# PATHOS_DriveConnectors.net
KiCad netlist of a schematic drawn in Altium Designer
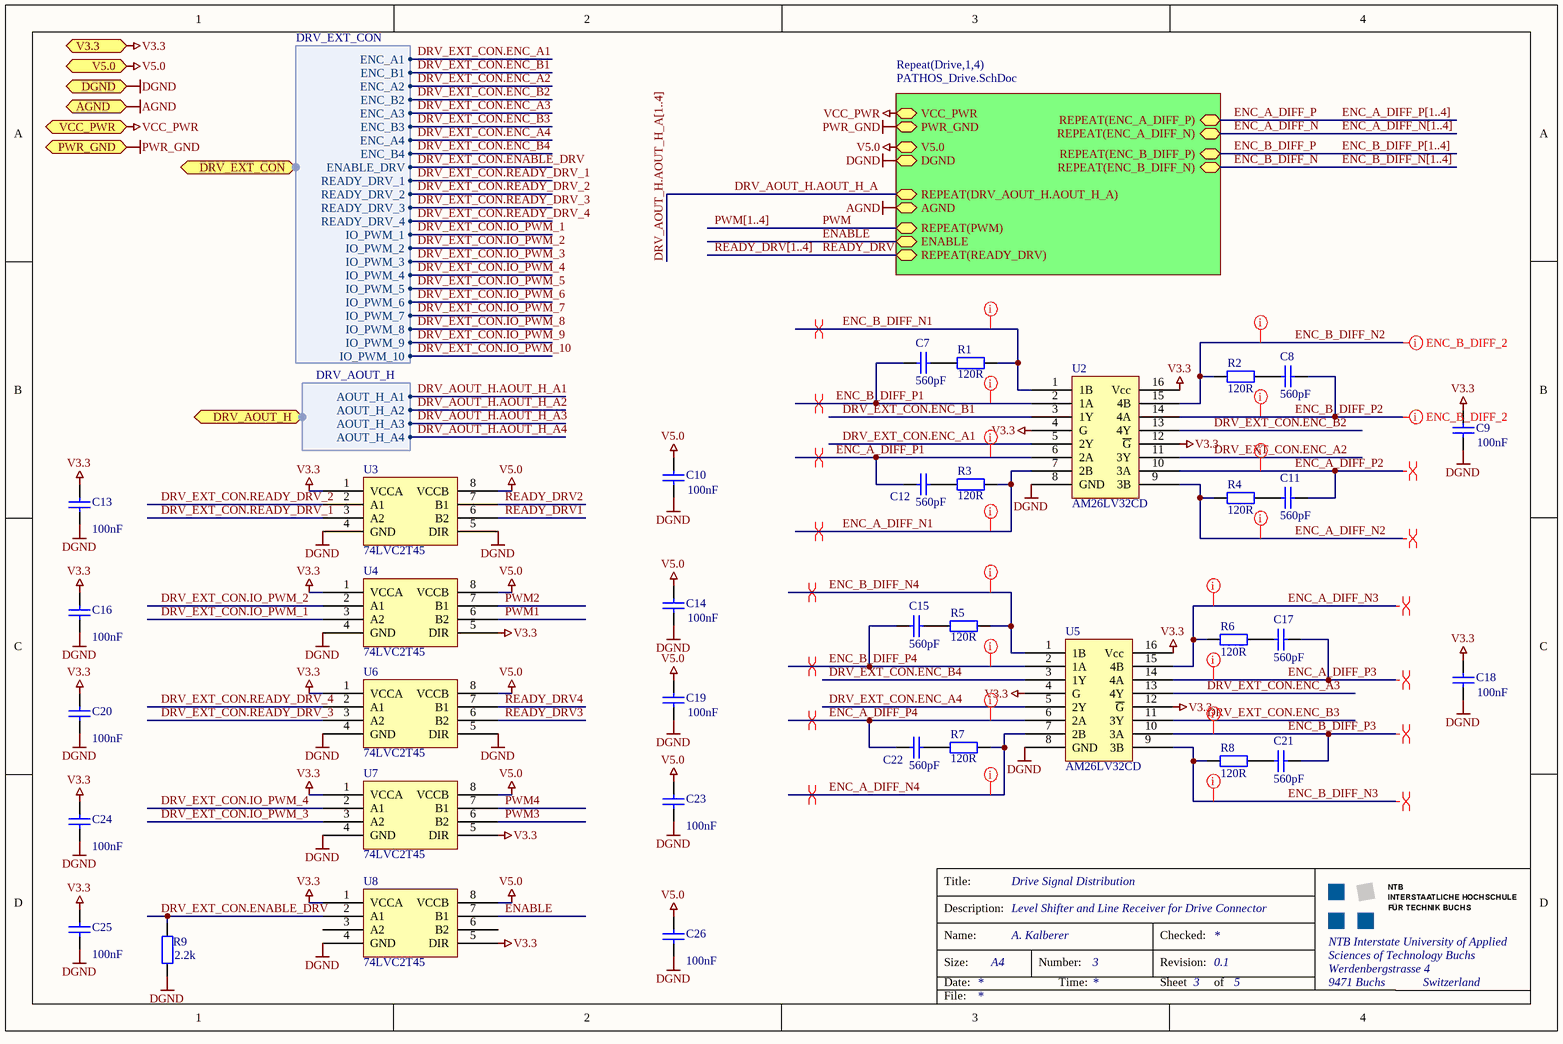
[diagram p0: PATHOS_DriveConnectors.SchDoc]

(export (version "E")
  (design (tool "Eeschema 10.0.6"))
  (components
    (comp (ref "C7")
      (value "560pF")
      (footprint "0603_3D")
      (description "Capacitor")
      (fields (field (name "Comment") "Cap") (field (name "PUBLISHER") "Altium Limited"))
      (libsource (lib "Miscellaneous Devices") (part "Cap"))
    )
    (comp (ref "C8")
      (value "560pF")
      (footprint "0603_3D")
      (description "Capacitor")
      (fields (field (name "Comment") "Cap") (field (name "PUBLISHER") "Altium Limited"))
      (libsource (lib "Miscellaneous Devices") (part "Cap"))
    )
    (comp (ref "C9")
      (value "100nF")
      (footprint "0603_3D")
      (description "Capacitor")
      (fields (field (name "Comment") "Cap") (field (name "PUBLISHER") "Altium Limited"))
      (libsource (lib "Miscellaneous Devices") (part "Cap"))
    )
    (comp (ref "C10")
      (value "100nF")
      (footprint "0603_3D")
      (description "Capacitor")
      (fields (field (name "Comment") "Cap") (field (name "PUBLISHER") "Altium Limited"))
      (libsource (lib "Miscellaneous Devices") (part "Cap"))
    )
    (comp (ref "C11")
      (value "560pF")
      (footprint "0603_3D")
      (description "Capacitor")
      (fields (field (name "Comment") "Cap") (field (name "PUBLISHER") "Altium Limited"))
      (libsource (lib "Miscellaneous Devices") (part "Cap"))
    )
    (comp (ref "C12")
      (value "560pF")
      (footprint "0603_3D")
      (description "Capacitor")
      (fields (field (name "Comment") "Cap") (field (name "PUBLISHER") "Altium Limited"))
      (libsource (lib "Miscellaneous Devices") (part "Cap"))
    )
    (comp (ref "C13")
      (value "100nF")
      (footprint "0603_3D")
      (description "Capacitor")
      (fields (field (name "Comment") "Cap") (field (name "PUBLISHER") "Altium Limited"))
      (libsource (lib "Miscellaneous Devices") (part "Cap"))
    )
    (comp (ref "C14")
      (value "100nF")
      (footprint "0603_3D")
      (description "Capacitor")
      (fields (field (name "Comment") "Cap") (field (name "PUBLISHER") "Altium Limited"))
      (libsource (lib "Miscellaneous Devices") (part "Cap"))
    )
    (comp (ref "C15")
      (value "560pF")
      (footprint "0603_3D")
      (description "Capacitor")
      (fields (field (name "Comment") "Cap") (field (name "PUBLISHER") "Altium Limited"))
      (libsource (lib "Miscellaneous Devices") (part "Cap"))
    )
    (comp (ref "C16")
      (value "100nF")
      (footprint "0603_3D")
      (description "Capacitor")
      (fields (field (name "Comment") "Cap") (field (name "PUBLISHER") "Altium Limited"))
      (libsource (lib "Miscellaneous Devices") (part "Cap"))
    )
    (comp (ref "C17")
      (value "560pF")
      (footprint "0603_3D")
      (description "Capacitor")
      (fields (field (name "Comment") "Cap") (field (name "PUBLISHER") "Altium Limited"))
      (libsource (lib "Miscellaneous Devices") (part "Cap"))
    )
    (comp (ref "C18")
      (value "100nF")
      (footprint "0603_3D")
      (description "Capacitor")
      (fields (field (name "Comment") "Cap") (field (name "PUBLISHER") "Altium Limited"))
      (libsource (lib "Miscellaneous Devices") (part "Cap"))
    )
    (comp (ref "C19")
      (value "100nF")
      (footprint "0603_3D")
      (description "Capacitor")
      (fields (field (name "Comment") "Cap") (field (name "PUBLISHER") "Altium Limited"))
      (libsource (lib "Miscellaneous Devices") (part "Cap"))
    )
    (comp (ref "C20")
      (value "100nF")
      (footprint "0603_3D")
      (description "Capacitor")
      (fields (field (name "Comment") "Cap") (field (name "PUBLISHER") "Altium Limited"))
      (libsource (lib "Miscellaneous Devices") (part "Cap"))
    )
    (comp (ref "C21")
      (value "560pF")
      (footprint "0603_3D")
      (description "Capacitor")
      (fields (field (name "Comment") "Cap") (field (name "PUBLISHER") "Altium Limited"))
      (libsource (lib "Miscellaneous Devices") (part "Cap"))
    )
    (comp (ref "C22")
      (value "560pF")
      (footprint "0603_3D")
      (description "Capacitor")
      (fields (field (name "Comment") "Cap") (field (name "PUBLISHER") "Altium Limited"))
      (libsource (lib "Miscellaneous Devices") (part "Cap"))
    )
    (comp (ref "C23")
      (value "100nF")
      (footprint "0603_3D")
      (description "Capacitor")
      (fields (field (name "Comment") "Cap") (field (name "PUBLISHER") "Altium Limited"))
      (libsource (lib "Miscellaneous Devices") (part "Cap"))
    )
    (comp (ref "C24")
      (value "100nF")
      (footprint "0603_3D")
      (description "Capacitor")
      (fields (field (name "Comment") "Cap") (field (name "PUBLISHER") "Altium Limited"))
      (libsource (lib "Miscellaneous Devices") (part "Cap"))
    )
    (comp (ref "C25")
      (value "100nF")
      (footprint "0603_3D")
      (description "Capacitor")
      (fields (field (name "Comment") "Cap") (field (name "PUBLISHER") "Altium Limited"))
      (libsource (lib "Miscellaneous Devices") (part "Cap"))
    )
    (comp (ref "C26")
      (value "100nF")
      (footprint "0603_3D")
      (description "Capacitor")
      (fields (field (name "Comment") "Cap") (field (name "PUBLISHER") "Altium Limited"))
      (libsource (lib "Miscellaneous Devices") (part "Cap"))
    )
    (comp (ref "R1")
      (value "120R")
      (footprint "0603_3D")
      (description "Resistor")
      (fields (field (name "Comment") "Res2") (field (name "PUBLISHER") "Altium Limited"))
      (libsource (lib "") (part "Res2_1"))
    )
    (comp (ref "R2")
      (value "120R")
      (footprint "0603_3D")
      (description "Resistor")
      (fields (field (name "Comment") "Res2") (field (name "PUBLISHER") "Altium Limited"))
      (libsource (lib "Miscellaneous Devices") (part "Res2"))
    )
    (comp (ref "R3")
      (value "120R")
      (footprint "0603_3D")
      (description "Resistor")
      (fields (field (name "Comment") "Res2") (field (name "PUBLISHER") "Altium Limited"))
      (libsource (lib "") (part "Res2_1"))
    )
    (comp (ref "R4")
      (value "120R")
      (footprint "0603_3D")
      (description "Resistor")
      (fields (field (name "Comment") "Res2") (field (name "PUBLISHER") "Altium Limited"))
      (libsource (lib "Miscellaneous Devices") (part "Res2"))
    )
    (comp (ref "R5")
      (value "120R")
      (footprint "0603_3D")
      (description "Resistor")
      (fields (field (name "Comment") "Res2") (field (name "PUBLISHER") "Altium Limited"))
      (libsource (lib "") (part "Res2_1"))
    )
    (comp (ref "R6")
      (value "120R")
      (footprint "0603_3D")
      (description "Resistor")
      (fields (field (name "Comment") "Res2") (field (name "PUBLISHER") "Altium Limited"))
      (libsource (lib "Miscellaneous Devices") (part "Res2"))
    )
    (comp (ref "R7")
      (value "120R")
      (footprint "0603_3D")
      (description "Resistor")
      (fields (field (name "Comment") "Res2") (field (name "PUBLISHER") "Altium Limited"))
      (libsource (lib "") (part "Res2_1"))
    )
    (comp (ref "R8")
      (value "120R")
      (footprint "0603_3D")
      (description "Resistor")
      (fields (field (name "Comment") "Res2") (field (name "PUBLISHER") "Altium Limited"))
      (libsource (lib "Miscellaneous Devices") (part "Res2"))
    )
    (comp (ref "R9")
      (value "2.2k")
      (footprint "0603_3D")
      (description "Resistor")
      (fields (field (name "Comment") "Res2") (field (name "PUBLISHER") "Altium Limited"))
      (libsource (lib "") (part "Res2_2"))
    )
    (comp (ref "U2")
      (value "AM26LV32CD")
      (footprint "SOP16")
      (libsource (lib "Pathos_Div") (part "AM26LV32CD"))
    )
    (comp (ref "U3")
      (value "74LVC2T45")
      (footprint "74LVC2T45")
      (description "SN74LVC2T45DCTR")
      (libsource (lib "Pathos_Div") (part "74LVC2T45"))
    )
    (comp (ref "U4")
      (value "74LVC2T45")
      (footprint "74LVC2T45")
      (description "SN74LVC2T45DCTR")
      (libsource (lib "Pathos_Div") (part "74LVC2T45"))
    )
    (comp (ref "U5")
      (value "AM26LV32CD")
      (footprint "SOP16")
      (libsource (lib "Pathos_Div") (part "AM26LV32CD"))
    )
    (comp (ref "U6")
      (value "74LVC2T45")
      (footprint "74LVC2T45")
      (description "SN74LVC2T45DCTR")
      (libsource (lib "Pathos_Div") (part "74LVC2T45"))
    )
    (comp (ref "U7")
      (value "74LVC2T45")
      (footprint "74LVC2T45")
      (description "SN74LVC2T45DCTR")
      (libsource (lib "Pathos_Div") (part "74LVC2T45"))
    )
    (comp (ref "U8")
      (value "74LVC2T45")
      (footprint "74LVC2T45")
      (description "SN74LVC2T45DCTR")
      (libsource (lib "Pathos_Div") (part "74LVC2T45"))
    )
  )
  (nets
    (net (code "9") (name "/DRV_EXT_CON.ENABLE_DRV") (class "Default")
      (node (ref "R9") (pin "2") (pinfunction "2_2") (pintype "passive"))
      (node (ref "U8") (pin "2") (pinfunction "A1_2") (pintype "passive"))
    )
    (net (code "10") (name "/DRV_EXT_CON.ENC_A1") (class "Default")
      (node (ref "U2") (pin "5") (pinfunction "2Y_5") (pintype "passive"))
    )
    (net (code "11") (name "/DRV_EXT_CON.ENC_A2") (class "Default")
      (node (ref "U2") (pin "11") (pinfunction "3Y_11") (pintype "passive"))
    )
    (net (code "12") (name "/DRV_EXT_CON.ENC_A3") (class "Default")
      (node (ref "U5") (pin "13") (pinfunction "4Y_13") (pintype "passive"))
    )
    (net (code "13") (name "/DRV_EXT_CON.ENC_A4") (class "Default")
      (node (ref "U5") (pin "5") (pinfunction "2Y_5") (pintype "passive"))
    )
    (net (code "14") (name "/DRV_EXT_CON.ENC_B1") (class "Default")
      (node (ref "U2") (pin "3") (pinfunction "1Y_3") (pintype "passive"))
    )
    (net (code "15") (name "/DRV_EXT_CON.ENC_B2") (class "Default")
      (node (ref "U2") (pin "13") (pinfunction "4Y_13") (pintype "passive"))
    )
    (net (code "16") (name "/DRV_EXT_CON.ENC_B3") (class "Default")
      (node (ref "U5") (pin "11") (pinfunction "3Y_11") (pintype "passive"))
    )
    (net (code "17") (name "/DRV_EXT_CON.ENC_B4") (class "Default")
      (node (ref "U5") (pin "3") (pinfunction "1Y_3") (pintype "passive"))
    )
    (net (code "18") (name "/DRV_EXT_CON.IO_PWM_1") (class "Default")
      (node (ref "U4") (pin "3") (pinfunction "A2_3") (pintype "passive"))
    )
    (net (code "19") (name "/DRV_EXT_CON.IO_PWM_2") (class "Default")
      (node (ref "U4") (pin "2") (pinfunction "A1_2") (pintype "passive"))
    )
    (net (code "20") (name "/DRV_EXT_CON.IO_PWM_3") (class "Default")
      (node (ref "U7") (pin "3") (pinfunction "A2_3") (pintype "passive"))
    )
    (net (code "21") (name "/DRV_EXT_CON.IO_PWM_4") (class "Default")
      (node (ref "U7") (pin "2") (pinfunction "A1_2") (pintype "passive"))
    )
    (net (code "28") (name "/DRV_EXT_CON.READY_DRV_1") (class "Default")
      (node (ref "U3") (pin "3") (pinfunction "A2_3") (pintype "passive"))
    )
    (net (code "29") (name "/DRV_EXT_CON.READY_DRV_2") (class "Default")
      (node (ref "U3") (pin "2") (pinfunction "A1_2") (pintype "passive"))
    )
    (net (code "30") (name "/DRV_EXT_CON.READY_DRV_3") (class "Default")
      (node (ref "U6") (pin "3") (pinfunction "A2_3") (pintype "passive"))
    )
    (net (code "31") (name "/DRV_EXT_CON.READY_DRV_4") (class "Default")
      (node (ref "U6") (pin "2") (pinfunction "A1_2") (pintype "passive"))
    )
    (net (code "32") (name "/ENABLE") (class "Default")
      (node (ref "U8") (pin "7") (pinfunction "B1_7") (pintype "passive"))
    )
    (net (code "34") (name "/ENC_A_DIFF_N1") (class "Default")
      (node (ref "R3") (pin "1") (pinfunction "1_1") (pintype "passive"))
      (node (ref "U2") (pin "7") (pinfunction "2B_7") (pintype "passive"))
    )
    (net (code "35") (name "/ENC_A_DIFF_N2") (class "Default")
      (node (ref "R4") (pin "1") (pinfunction "1_1") (pintype "passive"))
      (node (ref "U2") (pin "9") (pinfunction "3B_9") (pintype "passive"))
    )
    (net (code "36") (name "/ENC_A_DIFF_N3") (class "Default")
      (node (ref "R6") (pin "1") (pinfunction "1_1") (pintype "passive"))
      (node (ref "U5") (pin "15") (pinfunction "4B_15") (pintype "passive"))
    )
    (net (code "37") (name "/ENC_A_DIFF_N4") (class "Default")
      (node (ref "R7") (pin "1") (pinfunction "1_1") (pintype "passive"))
      (node (ref "U5") (pin "7") (pinfunction "2B_7") (pintype "passive"))
    )
    (net (code "40") (name "/ENC_A_DIFF_P1") (class "Default")
      (node (ref "C12") (pin "2") (pinfunction "2_2") (pintype "passive"))
      (node (ref "U2") (pin "6") (pinfunction "2A_6") (pintype "passive"))
    )
    (net (code "41") (name "/ENC_A_DIFF_P2") (class "Default")
      (node (ref "C11") (pin "1") (pinfunction "1_1") (pintype "passive"))
      (node (ref "U2") (pin "10") (pinfunction "3A_10") (pintype "passive"))
    )
    (net (code "42") (name "/ENC_A_DIFF_P3") (class "Default")
      (node (ref "C17") (pin "1") (pinfunction "1_1") (pintype "passive"))
      (node (ref "U5") (pin "14") (pinfunction "4A_14") (pintype "passive"))
    )
    (net (code "43") (name "/ENC_A_DIFF_P4") (class "Default")
      (node (ref "C22") (pin "2") (pinfunction "2_2") (pintype "passive"))
      (node (ref "U5") (pin "6") (pinfunction "2A_6") (pintype "passive"))
    )
    (net (code "46") (name "/ENC_B_DIFF_N1") (class "Default")
      (node (ref "R1") (pin "1") (pinfunction "1_1") (pintype "passive"))
      (node (ref "U2") (pin "1") (pinfunction "1B_1") (pintype "passive"))
    )
    (net (code "47") (name "/ENC_B_DIFF_N2") (class "Default")
      (node (ref "R2") (pin "1") (pinfunction "1_1") (pintype "passive"))
      (node (ref "U2") (pin "15") (pinfunction "4B_15") (pintype "passive"))
    )
    (net (code "48") (name "/ENC_B_DIFF_N3") (class "Default")
      (node (ref "R8") (pin "1") (pinfunction "1_1") (pintype "passive"))
      (node (ref "U5") (pin "9") (pinfunction "3B_9") (pintype "passive"))
    )
    (net (code "49") (name "/ENC_B_DIFF_N4") (class "Default")
      (node (ref "R5") (pin "1") (pinfunction "1_1") (pintype "passive"))
      (node (ref "U5") (pin "1") (pinfunction "1B_1") (pintype "passive"))
    )
    (net (code "52") (name "/ENC_B_DIFF_P1") (class "Default")
      (node (ref "C7") (pin "2") (pinfunction "2_2") (pintype "passive"))
      (node (ref "U2") (pin "2") (pinfunction "1A_2") (pintype "passive"))
    )
    (net (code "53") (name "/ENC_B_DIFF_P2") (class "Default")
      (node (ref "C8") (pin "1") (pinfunction "1_1") (pintype "passive"))
      (node (ref "U2") (pin "14") (pinfunction "4A_14") (pintype "passive"))
    )
    (net (code "54") (name "/ENC_B_DIFF_P3") (class "Default")
      (node (ref "C21") (pin "1") (pinfunction "1_1") (pintype "passive"))
      (node (ref "U5") (pin "10") (pinfunction "3A_10") (pintype "passive"))
    )
    (net (code "55") (name "/ENC_B_DIFF_P4") (class "Default")
      (node (ref "C15") (pin "2") (pinfunction "2_2") (pintype "passive"))
      (node (ref "U5") (pin "2") (pinfunction "1A_2") (pintype "passive"))
    )
    (net (code "58") (name "/PWM1") (class "Default")
      (node (ref "U4") (pin "6") (pinfunction "B2_6") (pintype "passive"))
    )
    (net (code "59") (name "/PWM2") (class "Default")
      (node (ref "U4") (pin "7") (pinfunction "B1_7") (pintype "passive"))
    )
    (net (code "60") (name "/PWM3") (class "Default")
      (node (ref "U7") (pin "6") (pinfunction "B2_6") (pintype "passive"))
    )
    (net (code "61") (name "/PWM4") (class "Default")
      (node (ref "U7") (pin "7") (pinfunction "B1_7") (pintype "passive"))
    )
    (net (code "64") (name "/READY_DRV1") (class "Default")
      (node (ref "U3") (pin "6") (pinfunction "B2_6") (pintype "passive"))
    )
    (net (code "65") (name "/READY_DRV2") (class "Default")
      (node (ref "U3") (pin "7") (pinfunction "B1_7") (pintype "passive"))
    )
    (net (code "66") (name "/READY_DRV3") (class "Default")
      (node (ref "U6") (pin "6") (pinfunction "B2_6") (pintype "passive"))
    )
    (net (code "67") (name "/READY_DRV4") (class "Default")
      (node (ref "U6") (pin "7") (pinfunction "B1_7") (pintype "passive"))
    )
    (net (code "72") (name "DGND") (class "Default")
      (node (ref "C10") (pin "1") (pinfunction "1_1") (pintype "passive"))
      (node (ref "C13") (pin "1") (pinfunction "1_1") (pintype "passive"))
      (node (ref "C14") (pin "1") (pinfunction "1_1") (pintype "passive"))
      (node (ref "C16") (pin "1") (pinfunction "1_1") (pintype "passive"))
      (node (ref "C18") (pin "1") (pinfunction "1_1") (pintype "passive"))
      (node (ref "C19") (pin "1") (pinfunction "1_1") (pintype "passive"))
      (node (ref "C20") (pin "1") (pinfunction "1_1") (pintype "passive"))
      (node (ref "C23") (pin "1") (pinfunction "1_1") (pintype "passive"))
      (node (ref "C24") (pin "1") (pinfunction "1_1") (pintype "passive"))
      (node (ref "C25") (pin "1") (pinfunction "1_1") (pintype "passive"))
      (node (ref "C26") (pin "1") (pinfunction "1_1") (pintype "passive"))
      (node (ref "C9") (pin "1") (pinfunction "1_1") (pintype "passive"))
      (node (ref "R9") (pin "1") (pinfunction "1_1") (pintype "passive"))
      (node (ref "U2") (pin "8") (pinfunction "GND_8") (pintype "passive"))
      (node (ref "U3") (pin "4") (pinfunction "GND_4") (pintype "passive"))
      (node (ref "U3") (pin "5") (pinfunction "DIR_5") (pintype "passive"))
      (node (ref "U4") (pin "4") (pinfunction "GND_4") (pintype "passive"))
      (node (ref "U5") (pin "8") (pinfunction "GND_8") (pintype "passive"))
      (node (ref "U6") (pin "4") (pinfunction "GND_4") (pintype "passive"))
      (node (ref "U6") (pin "5") (pinfunction "DIR_5") (pintype "passive"))
      (node (ref "U7") (pin "4") (pinfunction "GND_4") (pintype "passive"))
      (node (ref "U8") (pin "4") (pinfunction "GND_4") (pintype "passive"))
    )
    (net (code "73") (name "Net-(C7-Pad1)") (class "Default")
      (node (ref "C7") (pin "1") (pinfunction "1_1") (pintype "passive"))
      (node (ref "R1") (pin "2") (pinfunction "2_2") (pintype "passive"))
    )
    (net (code "74") (name "Net-(C8-Pad2)") (class "Default")
      (node (ref "C8") (pin "2") (pinfunction "2_2") (pintype "passive"))
      (node (ref "R2") (pin "2") (pinfunction "2_2") (pintype "passive"))
    )
    (net (code "75") (name "Net-(C11-Pad2)") (class "Default")
      (node (ref "C11") (pin "2") (pinfunction "2_2") (pintype "passive"))
      (node (ref "R4") (pin "2") (pinfunction "2_2") (pintype "passive"))
    )
    (net (code "76") (name "Net-(C12-Pad1)") (class "Default")
      (node (ref "C12") (pin "1") (pinfunction "1_1") (pintype "passive"))
      (node (ref "R3") (pin "2") (pinfunction "2_2") (pintype "passive"))
    )
    (net (code "77") (name "Net-(C15-Pad1)") (class "Default")
      (node (ref "C15") (pin "1") (pinfunction "1_1") (pintype "passive"))
      (node (ref "R5") (pin "2") (pinfunction "2_2") (pintype "passive"))
    )
    (net (code "78") (name "Net-(C17-Pad2)") (class "Default")
      (node (ref "C17") (pin "2") (pinfunction "2_2") (pintype "passive"))
      (node (ref "R6") (pin "2") (pinfunction "2_2") (pintype "passive"))
    )
    (net (code "79") (name "Net-(C21-Pad2)") (class "Default")
      (node (ref "C21") (pin "2") (pinfunction "2_2") (pintype "passive"))
      (node (ref "R8") (pin "2") (pinfunction "2_2") (pintype "passive"))
    )
    (net (code "80") (name "Net-(C22-Pad1)") (class "Default")
      (node (ref "C22") (pin "1") (pinfunction "1_1") (pintype "passive"))
      (node (ref "R7") (pin "2") (pinfunction "2_2") (pintype "passive"))
    )
    (net (code "82") (name "V3.3") (class "Default")
      (node (ref "C13") (pin "2") (pinfunction "2_2") (pintype "passive"))
      (node (ref "C16") (pin "2") (pinfunction "2_2") (pintype "passive"))
      (node (ref "C18") (pin "2") (pinfunction "2_2") (pintype "passive"))
      (node (ref "C20") (pin "2") (pinfunction "2_2") (pintype "passive"))
      (node (ref "C24") (pin "2") (pinfunction "2_2") (pintype "passive"))
      (node (ref "C25") (pin "2") (pinfunction "2_2") (pintype "passive"))
      (node (ref "C9") (pin "2") (pinfunction "2_2") (pintype "passive"))
      (node (ref "U2") (pin "12") (pinfunction "~{G}_12") (pintype "passive"))
      (node (ref "U2") (pin "16") (pinfunction "Vcc_16") (pintype "passive"))
      (node (ref "U2") (pin "4") (pinfunction "G_4") (pintype "passive"))
      (node (ref "U3") (pin "1") (pinfunction "VCCA_1") (pintype "passive"))
      (node (ref "U4") (pin "1") (pinfunction "VCCA_1") (pintype "passive"))
      (node (ref "U4") (pin "5") (pinfunction "DIR_5") (pintype "passive"))
      (node (ref "U5") (pin "12") (pinfunction "~{G}_12") (pintype "passive"))
      (node (ref "U5") (pin "16") (pinfunction "Vcc_16") (pintype "passive"))
      (node (ref "U5") (pin "4") (pinfunction "G_4") (pintype "passive"))
      (node (ref "U6") (pin "1") (pinfunction "VCCA_1") (pintype "passive"))
      (node (ref "U7") (pin "1") (pinfunction "VCCA_1") (pintype "passive"))
      (node (ref "U7") (pin "5") (pinfunction "DIR_5") (pintype "passive"))
      (node (ref "U8") (pin "1") (pinfunction "VCCA_1") (pintype "passive"))
      (node (ref "U8") (pin "5") (pinfunction "DIR_5") (pintype "passive"))
    )
    (net (code "83") (name "V5.0") (class "Default")
      (node (ref "C10") (pin "2") (pinfunction "2_2") (pintype "passive"))
      (node (ref "C14") (pin "2") (pinfunction "2_2") (pintype "passive"))
      (node (ref "C19") (pin "2") (pinfunction "2_2") (pintype "passive"))
      (node (ref "C23") (pin "2") (pinfunction "2_2") (pintype "passive"))
      (node (ref "C26") (pin "2") (pinfunction "2_2") (pintype "passive"))
      (node (ref "U3") (pin "8") (pinfunction "VCCB_8") (pintype "passive"))
      (node (ref "U4") (pin "8") (pinfunction "VCCB_8") (pintype "passive"))
      (node (ref "U6") (pin "8") (pinfunction "VCCB_8") (pintype "passive"))
      (node (ref "U7") (pin "8") (pinfunction "VCCB_8") (pintype "passive"))
      (node (ref "U8") (pin "8") (pinfunction "VCCB_8") (pintype "passive"))
    )
    (net (code "85") (name "unconnected-(U8-A2-Pad3)") (class "Default")
      (node (ref "U8") (pin "3") (pinfunction "A2_3") (pintype "passive"))
    )
    (net (code "86") (name "unconnected-(U8-B2-Pad6)") (class "Default")
      (node (ref "U8") (pin "6") (pinfunction "B2_6") (pintype "passive"))
    )
  )
)
